# Mainboard_ThermistorAmp.net
KiCad netlist of a schematic drawn in Altium Designer
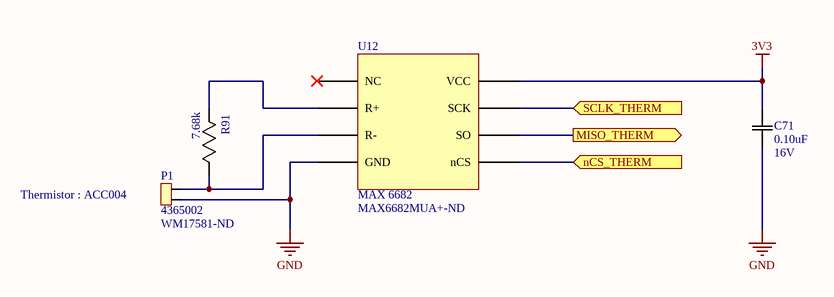
[diagram p0: Mainboard_ThermistorAmp.SchDoc]

(export (version "E")
  (design (tool "Eeschema 10.0.6"))
  (components
    (comp (ref "C71")
      (value "0.10uF")
      (footprint "0603")
      (description "CAP CER 0.10UF 16V X5R 0603/0805")
      (fields (field (name "TOLERANCE") "10%") (field (name "RATING") "16V"))
      (libsource (lib "AltiumLibraries") (part "CAP 0.10uF 16V"))
    )
    (comp (ref "P1")
      (value "4365002")
      (footprint "43650-02")
      (description "MOLEX MICROFIT 2CKT RIGHT THRU")
      (fields
        (field (name "MF") "MOLEX")
        (field (name "MP") "4365002XX")
        (field (name "SUPPLIER PART NUMBER 2") "WM17581-ND")
      )
      (libsource (lib "AltiumLibraries") (part "CN MOLEX 4365002XX"))
    )
    (comp (ref "R91")
      (value "7.68k")
      (footprint "0805")
      (description "RES SMD 7.68K OHM 0.1% 0.15W 0805")
      (fields (field (name "TOLERANCE") "5%"))
      (libsource (lib "AltiumLibraries") (part "RES 7.68k 0.15W"))
    )
    (comp (ref "U12")
      (value "MAX 6682")
      (footprint "8-MSOP")
      (description "MAX 6685 Thermistor - SPI converter, 8bit")
      (fields (field (name "SUPPLIER PART NUMBER 1") "MAX6682MUA+-ND"))
      (libsource (lib "AltiumLibraries") (part "MAX 6682"))
    )
  )
  (nets
    (net (code "1") (name "/MISO_THERM") (class "Default")
      (node (ref "U12") (pin "6") (pinfunction "SO_6") (pintype "passive"))
    )
    (net (code "2") (name "/SCLK_THERM") (class "Default")
      (node (ref "U12") (pin "7") (pinfunction "SCK_7") (pintype "passive"))
    )
    (net (code "3") (name "/nCS_THERM") (class "Default")
      (node (ref "U12") (pin "5") (pinfunction "nCS_5") (pintype "passive"))
    )
    (net (code "4") (name "3V3") (class "Default")
      (node (ref "C71") (pin "1") (pinfunction "C1_1") (pintype "passive"))
      (node (ref "U12") (pin "8") (pinfunction "VCC_8") (pintype "passive"))
    )
    (net (code "5") (name "GND") (class "Default")
      (node (ref "C71") (pin "2") (pinfunction "C2_2") (pintype "passive"))
      (node (ref "P1") (pin "1") (pinfunction "1_1") (pintype "passive"))
      (node (ref "U12") (pin "4") (pinfunction "GND_4") (pintype "passive"))
    )
    (net (code "6") (name "Net-(R91-R1)") (class "Default")
      (node (ref "P1") (pin "2") (pinfunction "2_2") (pintype "passive"))
      (node (ref "R91") (pin "1") (pinfunction "R1_1") (pintype "passive"))
      (node (ref "U12") (pin "3") (pinfunction "R-_3") (pintype "passive"))
    )
    (net (code "7") (name "Net-(R91-R2)") (class "Default")
      (node (ref "R91") (pin "2") (pinfunction "R2_2") (pintype "passive"))
      (node (ref "U12") (pin "2") (pinfunction "R+_2") (pintype "passive"))
    )
    (net (code "8") (name "unconnected-(U12-NC-Pad1)") (class "Default")
      (node (ref "U12") (pin "1") (pinfunction "NC_1") (pintype "passive+no_connect"))
    )
  )
)
